# I2C.net
KiCad netlist of a schematic drawn in Altium Designer
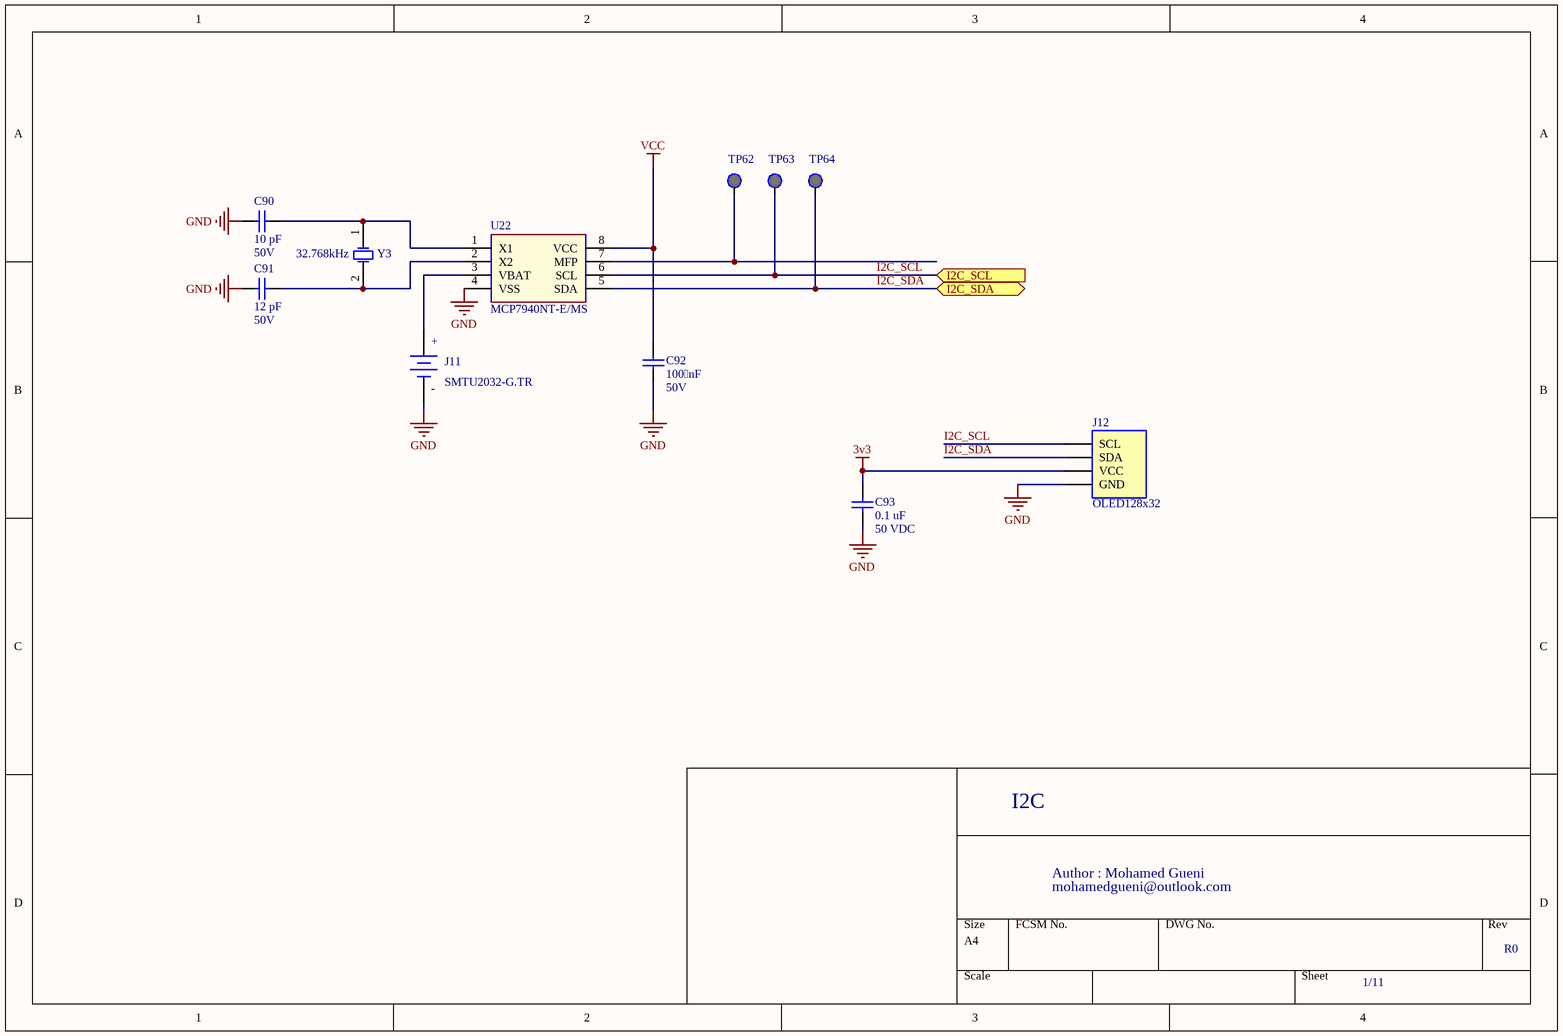
[diagram p0: I2C.SchDoc]

(export (version "E")
  (design (tool "Eeschema 10.0.6"))
  (components
    (comp (ref "C90")
      (value "~")
      (footprint "CAPC1608N")
      (fields
        (field (name "PART NUMBER") "CAP-000000033")
        (field (name "VALUE 1") "10 pF")
        (field (name "VALUE 2") "50V")
      )
      (libsource (lib "DB") (part "Capacitor"))
    )
    (comp (ref "C91")
      (value "~")
      (footprint "CAPC1608N")
      (fields
        (field (name "PART NUMBER") "CAP-000000032")
        (field (name "VALUE 1") "12 pF")
        (field (name "VALUE 2") "50V")
      )
      (libsource (lib "DB") (part "Capacitor"))
    )
    (comp (ref "C92")
      (value "GRM188R71H104KA93D")
      (footprint "CAPC1608N")
      (fields
        (field (name "PART NUMBER") "CAP-000000017")
        (field (name "VALUE 1") "100 nF")
        (field (name "VALUE 2") "50V")
      )
      (libsource (lib "DB") (part "Capacitor"))
    )
    (comp (ref "C93")
      (value "Capacitor")
      (footprint "CAPC1608N")
      (fields
        (field (name "PART NUMBER") "CAP-000000003")
        (field (name "VALUE 1") "0.1 uF")
        (field (name "VALUE 2") "50 VDC")
      )
      (libsource (lib "DB") (part "Capacitor"))
    )
    (comp (ref "J11")
      (value "SMTU2032-G.TR")
      (footprint "SMTU2032GTR")
      (fields (field (name "PART NUMBER") "CON-000000012"))
      (libsource (lib "DB") (part "SMTU2032-G.TR"))
    )
    (comp (ref "J12")
      (value "OLED128x32")
      (footprint "OLED128x32")
      (fields (field (name "PART NUMBER") "CON-000000009"))
      (libsource (lib "DB") (part "OLED128x32"))
    )
    (comp (ref "TP62")
      (value "Test Point")
      (footprint "TP")
      (fields (field (name "PART NUMBER") "MIS-000000002"))
      (libsource (lib "DB") (part "TP"))
    )
    (comp (ref "TP63")
      (value "Test Point")
      (footprint "TP")
      (fields (field (name "PART NUMBER") "MIS-000000002"))
      (libsource (lib "DB") (part "TP"))
    )
    (comp (ref "TP64")
      (value "Test Point")
      (footprint "TP")
      (fields (field (name "PART NUMBER") "MIS-000000002"))
      (libsource (lib "DB") (part "TP"))
    )
    (comp (ref "U22")
      (value "MCP7940NT-E/MS")
      (footprint "SOP65P490X110-8N")
      (description "Real Time Clock I2C GP RTCC 64B SRAM, EXT")
      (fields (field (name "PART NUMBER") "GIC-000000014"))
      (libsource (lib "DB") (part "MCP7940NT-E_MS"))
    )
    (comp (ref "Y3")
      (value "XT1312HHRXX32K76E")
      (footprint "XT1312HHRXX32K76E")
      (fields (field (name "PART NUMBER") "Y-000000006") (field (name "VALUE 1") "32.768kHz"))
      (libsource (lib "DB") (part "XTAL"))
    )
  )
  (nets
    (net (code "1") (name "/I2C_SCL") (class "Default")
      (node (ref "J12") (pin "4") (pinfunction "SCL_4") (pintype "passive"))
      (node (ref "TP63") (pin "1") (pinfunction "1_1") (pintype "passive"))
      (node (ref "U22") (pin "6") (pinfunction "SCL_6") (pintype "passive"))
    )
    (net (code "2") (name "/I2C_SDA") (class "Default")
      (node (ref "J12") (pin "3") (pinfunction "SDA_3") (pintype "passive"))
      (node (ref "TP64") (pin "1") (pinfunction "1_1") (pintype "passive"))
      (node (ref "U22") (pin "5") (pinfunction "SDA_5") (pintype "passive"))
    )
    (net (code "3") (name "3v3") (class "Default")
      (node (ref "C93") (pin "2") (pinfunction "2_2") (pintype "passive"))
      (node (ref "J12") (pin "2") (pinfunction "VCC_2") (pintype "passive"))
    )
    (net (code "4") (name "GND") (class "Default")
      (node (ref "C90") (pin "1") (pinfunction "1_1") (pintype "passive"))
      (node (ref "C91") (pin "1") (pinfunction "1_1") (pintype "passive"))
      (node (ref "C92") (pin "1") (pinfunction "1_1") (pintype "passive"))
      (node (ref "C93") (pin "1") (pinfunction "1_1") (pintype "passive"))
      (node (ref "J11") (pin "2") (pinfunction "-_2") (pintype "passive"))
      (node (ref "J12") (pin "1") (pinfunction "GND_1") (pintype "passive"))
      (node (ref "U22") (pin "4") (pinfunction "VSS_4") (pintype "passive"))
    )
    (net (code "5") (name "Net-(J11-+)") (class "Default")
      (node (ref "J11") (pin "1") (pinfunction "+_1") (pintype "passive"))
      (node (ref "U22") (pin "3") (pinfunction "VBAT_3") (pintype "passive"))
    )
    (net (code "6") (name "Net-(U22-MFP)") (class "Default")
      (node (ref "TP62") (pin "1") (pinfunction "1_1") (pintype "passive"))
      (node (ref "U22") (pin "7") (pinfunction "MFP_7") (pintype "passive"))
    )
    (net (code "7") (name "Net-(U22-X1)") (class "Default")
      (node (ref "C90") (pin "2") (pinfunction "2_2") (pintype "passive"))
      (node (ref "U22") (pin "1") (pinfunction "X1_1") (pintype "passive"))
      (node (ref "Y3") (pin "1") (pinfunction "OSC1_1") (pintype "passive"))
    )
    (net (code "8") (name "Net-(U22-X2)") (class "Default")
      (node (ref "C91") (pin "2") (pinfunction "2_2") (pintype "passive"))
      (node (ref "U22") (pin "2") (pinfunction "X2_2") (pintype "passive"))
      (node (ref "Y3") (pin "2") (pinfunction "OSC2_2") (pintype "passive"))
    )
    (net (code "9") (name "VCC") (class "Default")
      (node (ref "C92") (pin "2") (pinfunction "2_2") (pintype "passive"))
      (node (ref "U22") (pin "8") (pinfunction "VCC_8") (pintype "passive"))
    )
  )
)
